# Grove_-_Mini_Fan_v1_0.net
KiCad netlist of a schematic drawn in EAGLE
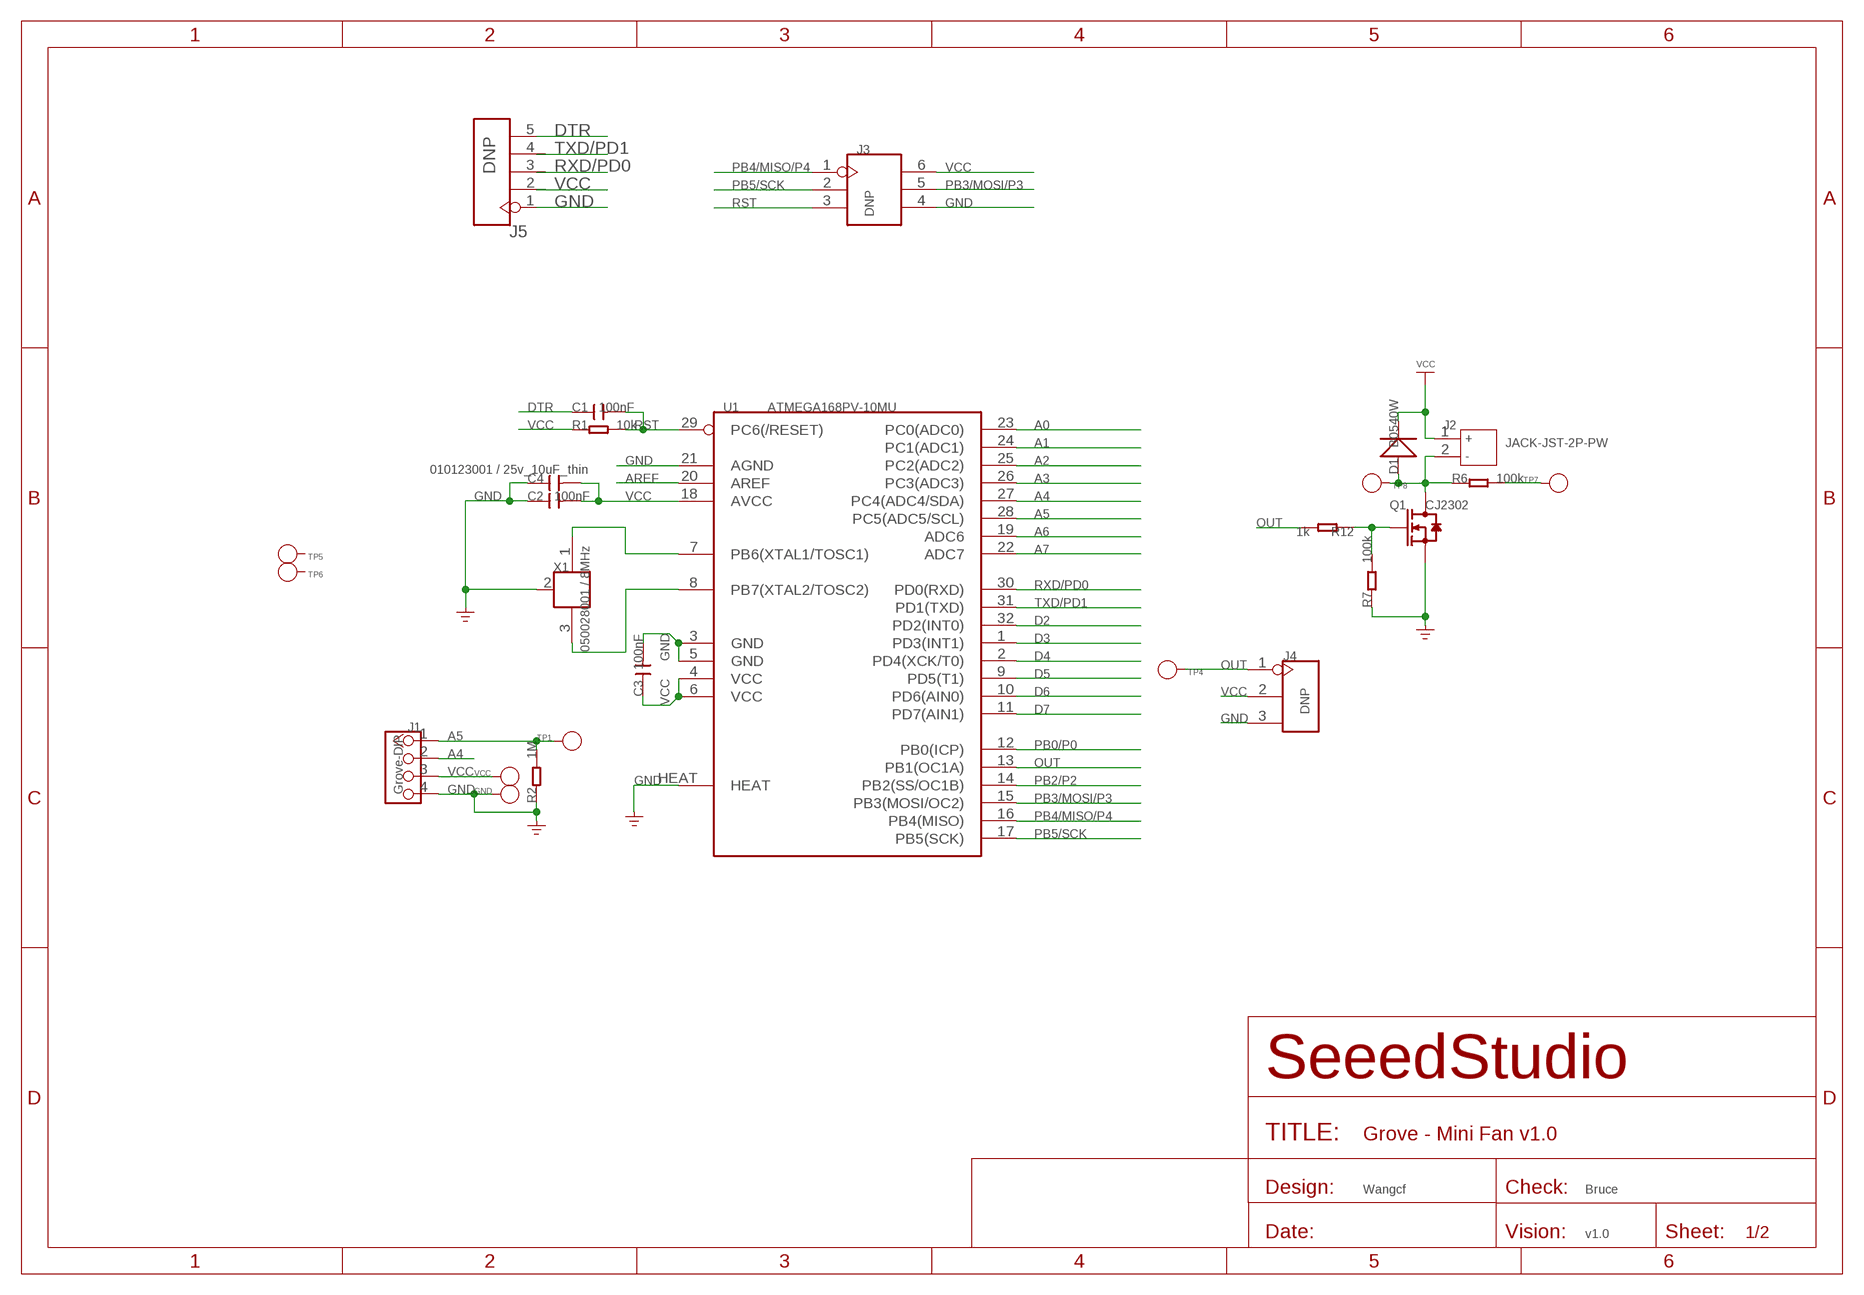
[diagram p0: schematic, sheet 1]

(export (version "E")
  (design (tool "Eeschema 10.0.6"))
  (components
    (comp (ref "C1")
      (value "100nF")
      (footprint "eagle-import:C0603")
      (libsource (lib "eagle-import") (part "C-0603"))
    )
    (comp (ref "C2")
      (value "100nF")
      (footprint "eagle-import:C0603")
      (libsource (lib "eagle-import") (part "C-0603"))
    )
    (comp (ref "C3")
      (value "100nF")
      (footprint "eagle-import:C0603")
      (libsource (lib "eagle-import") (part "C-0603"))
    )
    (comp (ref "C4")
      (value "010123001 / 25v_10uF_thin")
      (footprint "eagle-import:C0805")
      (libsource (lib "eagle-import") (part "C-0805"))
    )
    (comp (ref "D1")
      (value "B0540W")
      (footprint "eagle-import:SOD123")
      (libsource (lib "eagle-import") (part "D'1206'"))
    )
    (comp (ref "GND")
      (value "PAD-TEST-POINT'4545'")
      (footprint "eagle-import:TP_4545")
      (fields (field (name "PARTNO") "DNP"))
      (libsource (lib "eagle-import") (part "PAD-TEST-POINT'4545'"))
    )
    (comp (ref "J1")
      (value "Grove-DIP")
      (footprint "eagle-import:4P-2.0")
      (libsource (lib "eagle-import") (part "TWIG-4P-2.0-2.0"))
    )
    (comp (ref "J2")
      (value "JACK-JST-2P-PW")
      (footprint "eagle-import:JST-2.0")
      (libsource (lib "eagle-import") (part "JACK-JST-2P-PW'2.0'"))
    )
    (comp (ref "J3")
      (value "DNP")
      (footprint "eagle-import:2X3P-2.0")
      (libsource (lib "eagle-import") (part "HEADER-2X3P-2.0"))
    )
    (comp (ref "J4")
      (value "DNP")
      (footprint "eagle-import:3P-2.54")
      (libsource (lib "eagle-import") (part "HEADER-3P-2.54"))
    )
    (comp (ref "J5")
      (value "DNP")
      (footprint "eagle-import:5P-2.54")
      (libsource (lib "eagle-import") (part "HEADER-5P-2.54"))
    )
    (comp (ref "Q1")
      (value "CJ2302")
      (footprint "eagle-import:SOT23")
      (libsource (lib "eagle-import") (part "MOSFET-N'SOT23'"))
    )
    (comp (ref "R1")
      (value "10k")
      (footprint "eagle-import:R0603")
      (libsource (lib "eagle-import") (part "R-0603"))
    )
    (comp (ref "R2")
      (value "1M")
      (footprint "eagle-import:R0603")
      (libsource (lib "eagle-import") (part "R-0603"))
    )
    (comp (ref "R6")
      (value "100k")
      (footprint "eagle-import:R0603")
      (libsource (lib "eagle-import") (part "R-0603"))
    )
    (comp (ref "R7")
      (value "100k")
      (footprint "eagle-import:R0603")
      (libsource (lib "eagle-import") (part "R-0603"))
    )
    (comp (ref "R12")
      (value "1k")
      (footprint "eagle-import:R0603")
      (libsource (lib "eagle-import") (part "R-0603"))
    )
    (comp (ref "TP1")
      (value "PAD-TEST-POINT'4545'")
      (footprint "eagle-import:TP_4545")
      (fields (field (name "PARTNO") "DNP"))
      (libsource (lib "eagle-import") (part "PAD-TEST-POINT'4545'"))
    )
    (comp (ref "TP4")
      (value "PAD-TEST-POINT'4545'")
      (footprint "eagle-import:TP_4545")
      (fields (field (name "PARTNO") "DNP"))
      (libsource (lib "eagle-import") (part "PAD-TEST-POINT'4545'"))
    )
    (comp (ref "TP5")
      (value "PAD-TEST-POINT'4545'")
      (footprint "eagle-import:TP_4545")
      (fields (field (name "PARTNO") "DNP"))
      (libsource (lib "eagle-import") (part "PAD-TEST-POINT'4545'"))
    )
    (comp (ref "TP6")
      (value "PAD-TEST-POINT'4545'")
      (footprint "eagle-import:TP_4545")
      (fields (field (name "PARTNO") "DNP"))
      (libsource (lib "eagle-import") (part "PAD-TEST-POINT'4545'"))
    )
    (comp (ref "TP7")
      (value "PAD-TEST-POINT'4545'")
      (footprint "eagle-import:TP_4545")
      (fields (field (name "PARTNO") "DNP"))
      (libsource (lib "eagle-import") (part "PAD-TEST-POINT'4545'"))
    )
    (comp (ref "TP8")
      (value "PAD-TEST-POINT'4545'")
      (footprint "eagle-import:TP_4545")
      (fields (field (name "PARTNO") "DNP"))
      (libsource (lib "eagle-import") (part "PAD-TEST-POINT'4545'"))
    )
    (comp (ref "U1")
      (value "ATMEGA168PV-10MU")
      (footprint "eagle-import:MLF32X")
      (libsource (lib "eagle-import") (part "MEGA8"))
    )
    (comp (ref "VCC")
      (value "PAD-TEST-POINT'4545'")
      (footprint "eagle-import:TP_4545")
      (fields (field (name "PARTNO") "DNP"))
      (libsource (lib "eagle-import") (part "PAD-TEST-POINT'4545'"))
    )
    (comp (ref "X1")
      (value "050028001 / 8MHz")
      (footprint "eagle-import:XTAL_3X2")
      (libsource (lib "eagle-import") (part "XTAL_NCVER"))
    )
  )
  (nets
    (net (code "1") (name "A0") (class "Default")
      (node (ref "U1") (pin "23") (pinfunction "PC0(ADC0)_23") (pintype "bidirectional"))
    )
    (net (code "2") (name "A1") (class "Default")
      (node (ref "U1") (pin "24") (pinfunction "PC1(ADC1)_24") (pintype "bidirectional"))
    )
    (net (code "3") (name "A2") (class "Default")
      (node (ref "U1") (pin "25") (pinfunction "PC2(ADC2)_25") (pintype "bidirectional"))
    )
    (net (code "4") (name "A3") (class "Default")
      (node (ref "U1") (pin "26") (pinfunction "PC3(ADC3)_26") (pintype "bidirectional"))
    )
    (net (code "5") (name "A4") (class "Default")
      (node (ref "J1") (pin "2") (pinfunction "2_2") (pintype "bidirectional"))
      (node (ref "U1") (pin "27") (pinfunction "PC4(ADC4/SDA)_27") (pintype "bidirectional"))
    )
    (net (code "6") (name "A5") (class "Default")
      (node (ref "J1") (pin "1") (pinfunction "1_1") (pintype "bidirectional"))
      (node (ref "R2") (pin "2") (pinfunction "2_2") (pintype "passive"))
      (node (ref "TP1") (pin "T") (pinfunction "T_T") (pintype "bidirectional"))
      (node (ref "U1") (pin "28") (pinfunction "PC5(ADC5/SCL)_28") (pintype "bidirectional"))
    )
    (net (code "7") (name "A6") (class "Default")
      (node (ref "U1") (pin "19") (pinfunction "ADC6_19") (pintype "bidirectional"))
    )
    (net (code "8") (name "A7") (class "Default")
      (node (ref "U1") (pin "22") (pinfunction "ADC7_22") (pintype "bidirectional"))
    )
    (net (code "9") (name "AREF") (class "Default")
      (node (ref "U1") (pin "20") (pinfunction "AREF_20") (pintype "bidirectional"))
    )
    (net (code "10") (name "D2") (class "Default")
      (node (ref "U1") (pin "32") (pinfunction "PD2(INT0)_32") (pintype "bidirectional"))
    )
    (net (code "11") (name "D3") (class "Default")
      (node (ref "U1") (pin "1") (pinfunction "PD3(INT1)_1") (pintype "bidirectional"))
    )
    (net (code "12") (name "D4") (class "Default")
      (node (ref "U1") (pin "2") (pinfunction "PD4(XCK/T0)_2") (pintype "bidirectional"))
    )
    (net (code "13") (name "D5") (class "Default")
      (node (ref "U1") (pin "9") (pinfunction "PD5(T1)_9") (pintype "bidirectional"))
    )
    (net (code "14") (name "D6") (class "Default")
      (node (ref "U1") (pin "10") (pinfunction "PD6(AIN0)_10") (pintype "bidirectional"))
    )
    (net (code "15") (name "D7") (class "Default")
      (node (ref "U1") (pin "11") (pinfunction "PD7(AIN1)_11") (pintype "bidirectional"))
    )
    (net (code "16") (name "DTR") (class "Default")
      (node (ref "C1") (pin "1") (pinfunction "1_1") (pintype "passive"))
      (node (ref "J5") (pin "5") (pinfunction "5_5") (pintype "bidirectional"))
    )
    (net (code "17") (name "GND") (class "Default")
      (node (ref "C2") (pin "1") (pinfunction "1_1") (pintype "passive"))
      (node (ref "C3") (pin "2") (pinfunction "2_2") (pintype "passive"))
      (node (ref "C4") (pin "1") (pinfunction "1_1") (pintype "passive"))
      (node (ref "GND") (pin "T") (pinfunction "T_T") (pintype "bidirectional"))
      (node (ref "J1") (pin "4") (pinfunction "4_4") (pintype "bidirectional"))
      (node (ref "J3") (pin "4") (pinfunction "4_4") (pintype "bidirectional"))
      (node (ref "J4") (pin "3") (pinfunction "P$3_3") (pintype "bidirectional"))
      (node (ref "J5") (pin "1") (pinfunction "1_1") (pintype "bidirectional"))
      (node (ref "Q1") (pin "2") (pinfunction "S_2") (pintype "passive"))
      (node (ref "R2") (pin "1") (pinfunction "1_1") (pintype "passive"))
      (node (ref "R7") (pin "1") (pinfunction "1_1") (pintype "passive"))
      (node (ref "U1") (pin "21") (pinfunction "AGND_21") (pintype "bidirectional"))
      (node (ref "U1") (pin "3") (pinfunction "GND_3") (pintype "bidirectional"))
      (node (ref "U1") (pin "5") (pinfunction "GND_5") (pintype "bidirectional"))
      (node (ref "U1") (pin "HEAT") (pinfunction "HEAT_HEAT") (pintype "bidirectional"))
      (node (ref "X1") (pin "2") (pinfunction "GND_2") (pintype "bidirectional"))
    )
    (net (code "18") (name "Net-(J2-P$2)") (class "Default")
      (node (ref "D1") (pin "+") (pinfunction "+_+") (pintype "passive"))
      (node (ref "J2") (pin "2") (pinfunction "P$2_2") (pintype "bidirectional"))
      (node (ref "Q1") (pin "3") (pinfunction "D_3") (pintype "passive"))
      (node (ref "R6") (pin "1") (pinfunction "1_1") (pintype "passive"))
      (node (ref "TP8") (pin "T") (pinfunction "T_T") (pintype "bidirectional"))
    )
    (net (code "19") (name "Net-(Q1-G)") (class "Default")
      (node (ref "Q1") (pin "1") (pinfunction "G_1") (pintype "passive"))
      (node (ref "R12") (pin "1") (pinfunction "1_1") (pintype "passive"))
      (node (ref "R7") (pin "2") (pinfunction "2_2") (pintype "passive"))
    )
    (net (code "20") (name "Net-(R6-Pad2)") (class "Default")
      (node (ref "R6") (pin "2") (pinfunction "2_2") (pintype "passive"))
      (node (ref "TP7") (pin "T") (pinfunction "T_T") (pintype "bidirectional"))
    )
    (net (code "21") (name "Net-(U1-PB6(XTAL1{slash}TOSC1))") (class "Default")
      (node (ref "U1") (pin "7") (pinfunction "PB6(XTAL1/TOSC1)_7") (pintype "bidirectional"))
      (node (ref "X1") (pin "1") (pinfunction "1_1") (pintype "bidirectional"))
    )
    (net (code "22") (name "Net-(U1-PB7(XTAL2{slash}TOSC2))") (class "Default")
      (node (ref "U1") (pin "8") (pinfunction "PB7(XTAL2/TOSC2)_8") (pintype "bidirectional"))
      (node (ref "X1") (pin "3") (pinfunction "2_3") (pintype "bidirectional"))
    )
    (net (code "23") (name "OUT") (class "Default")
      (node (ref "J4") (pin "1") (pinfunction "P$1_1") (pintype "bidirectional"))
      (node (ref "R12") (pin "2") (pinfunction "2_2") (pintype "passive"))
      (node (ref "TP4") (pin "T") (pinfunction "T_T") (pintype "bidirectional"))
      (node (ref "U1") (pin "13") (pinfunction "PB1(OC1A)_13") (pintype "bidirectional"))
    )
    (net (code "24") (name "PB0{slash}P0") (class "Default")
      (node (ref "U1") (pin "12") (pinfunction "PB0(ICP)_12") (pintype "bidirectional"))
    )
    (net (code "25") (name "PB2{slash}P2") (class "Default")
      (node (ref "U1") (pin "14") (pinfunction "PB2(SS/OC1B)_14") (pintype "bidirectional"))
    )
    (net (code "26") (name "PB3{slash}MOSI{slash}P3") (class "Default")
      (node (ref "J3") (pin "5") (pinfunction "5_5") (pintype "bidirectional"))
      (node (ref "U1") (pin "15") (pinfunction "PB3(MOSI/OC2)_15") (pintype "bidirectional"))
    )
    (net (code "27") (name "PB4{slash}MISO{slash}P4") (class "Default")
      (node (ref "J3") (pin "1") (pinfunction "1_1") (pintype "bidirectional"))
      (node (ref "U1") (pin "16") (pinfunction "PB4(MISO)_16") (pintype "bidirectional"))
    )
    (net (code "28") (name "PB5{slash}SCK") (class "Default")
      (node (ref "J3") (pin "2") (pinfunction "2_2") (pintype "bidirectional"))
      (node (ref "U1") (pin "17") (pinfunction "PB5(SCK)_17") (pintype "bidirectional"))
    )
    (net (code "29") (name "RST") (class "Default")
      (node (ref "C1") (pin "2") (pinfunction "2_2") (pintype "passive"))
      (node (ref "J3") (pin "3") (pinfunction "3_3") (pintype "bidirectional"))
      (node (ref "R1") (pin "2") (pinfunction "2_2") (pintype "passive"))
      (node (ref "U1") (pin "29") (pinfunction "PC6(/RESET)_29") (pintype "bidirectional"))
    )
    (net (code "30") (name "RXD{slash}PD0") (class "Default")
      (node (ref "J5") (pin "3") (pinfunction "3_3") (pintype "bidirectional"))
      (node (ref "U1") (pin "30") (pinfunction "PD0(RXD)_30") (pintype "bidirectional"))
    )
    (net (code "31") (name "TXD{slash}PD1") (class "Default")
      (node (ref "J5") (pin "4") (pinfunction "4_4") (pintype "bidirectional"))
      (node (ref "U1") (pin "31") (pinfunction "PD1(TXD)_31") (pintype "bidirectional"))
    )
    (net (code "32") (name "VCC") (class "Default")
      (node (ref "C2") (pin "2") (pinfunction "2_2") (pintype "passive"))
      (node (ref "C3") (pin "1") (pinfunction "1_1") (pintype "passive"))
      (node (ref "C4") (pin "2") (pinfunction "2_2") (pintype "passive"))
      (node (ref "D1") (pin "-") (pinfunction "-_-") (pintype "passive"))
      (node (ref "J1") (pin "3") (pinfunction "3_3") (pintype "bidirectional"))
      (node (ref "J2") (pin "1") (pinfunction "P$1_1") (pintype "bidirectional"))
      (node (ref "J3") (pin "6") (pinfunction "6_6") (pintype "bidirectional"))
      (node (ref "J4") (pin "2") (pinfunction "P$2_2") (pintype "bidirectional"))
      (node (ref "J5") (pin "2") (pinfunction "2_2") (pintype "bidirectional"))
      (node (ref "R1") (pin "1") (pinfunction "1_1") (pintype "passive"))
      (node (ref "U1") (pin "18") (pinfunction "AVCC_18") (pintype "bidirectional"))
      (node (ref "U1") (pin "4") (pinfunction "VCC_4") (pintype "bidirectional"))
      (node (ref "U1") (pin "6") (pinfunction "VCC_6") (pintype "bidirectional"))
      (node (ref "VCC") (pin "T") (pinfunction "T_T") (pintype "bidirectional"))
    )
    (net (code "33") (name "unconnected-(TP5-PadT)") (class "Default")
      (node (ref "TP5") (pin "T") (pinfunction "T_T") (pintype "bidirectional"))
    )
    (net (code "34") (name "unconnected-(TP6-PadT)") (class "Default")
      (node (ref "TP6") (pin "T") (pinfunction "T_T") (pintype "bidirectional"))
    )
  )
)
